# BBPS_SMD.net
KiCad netlist of a schematic drawn in EAGLE
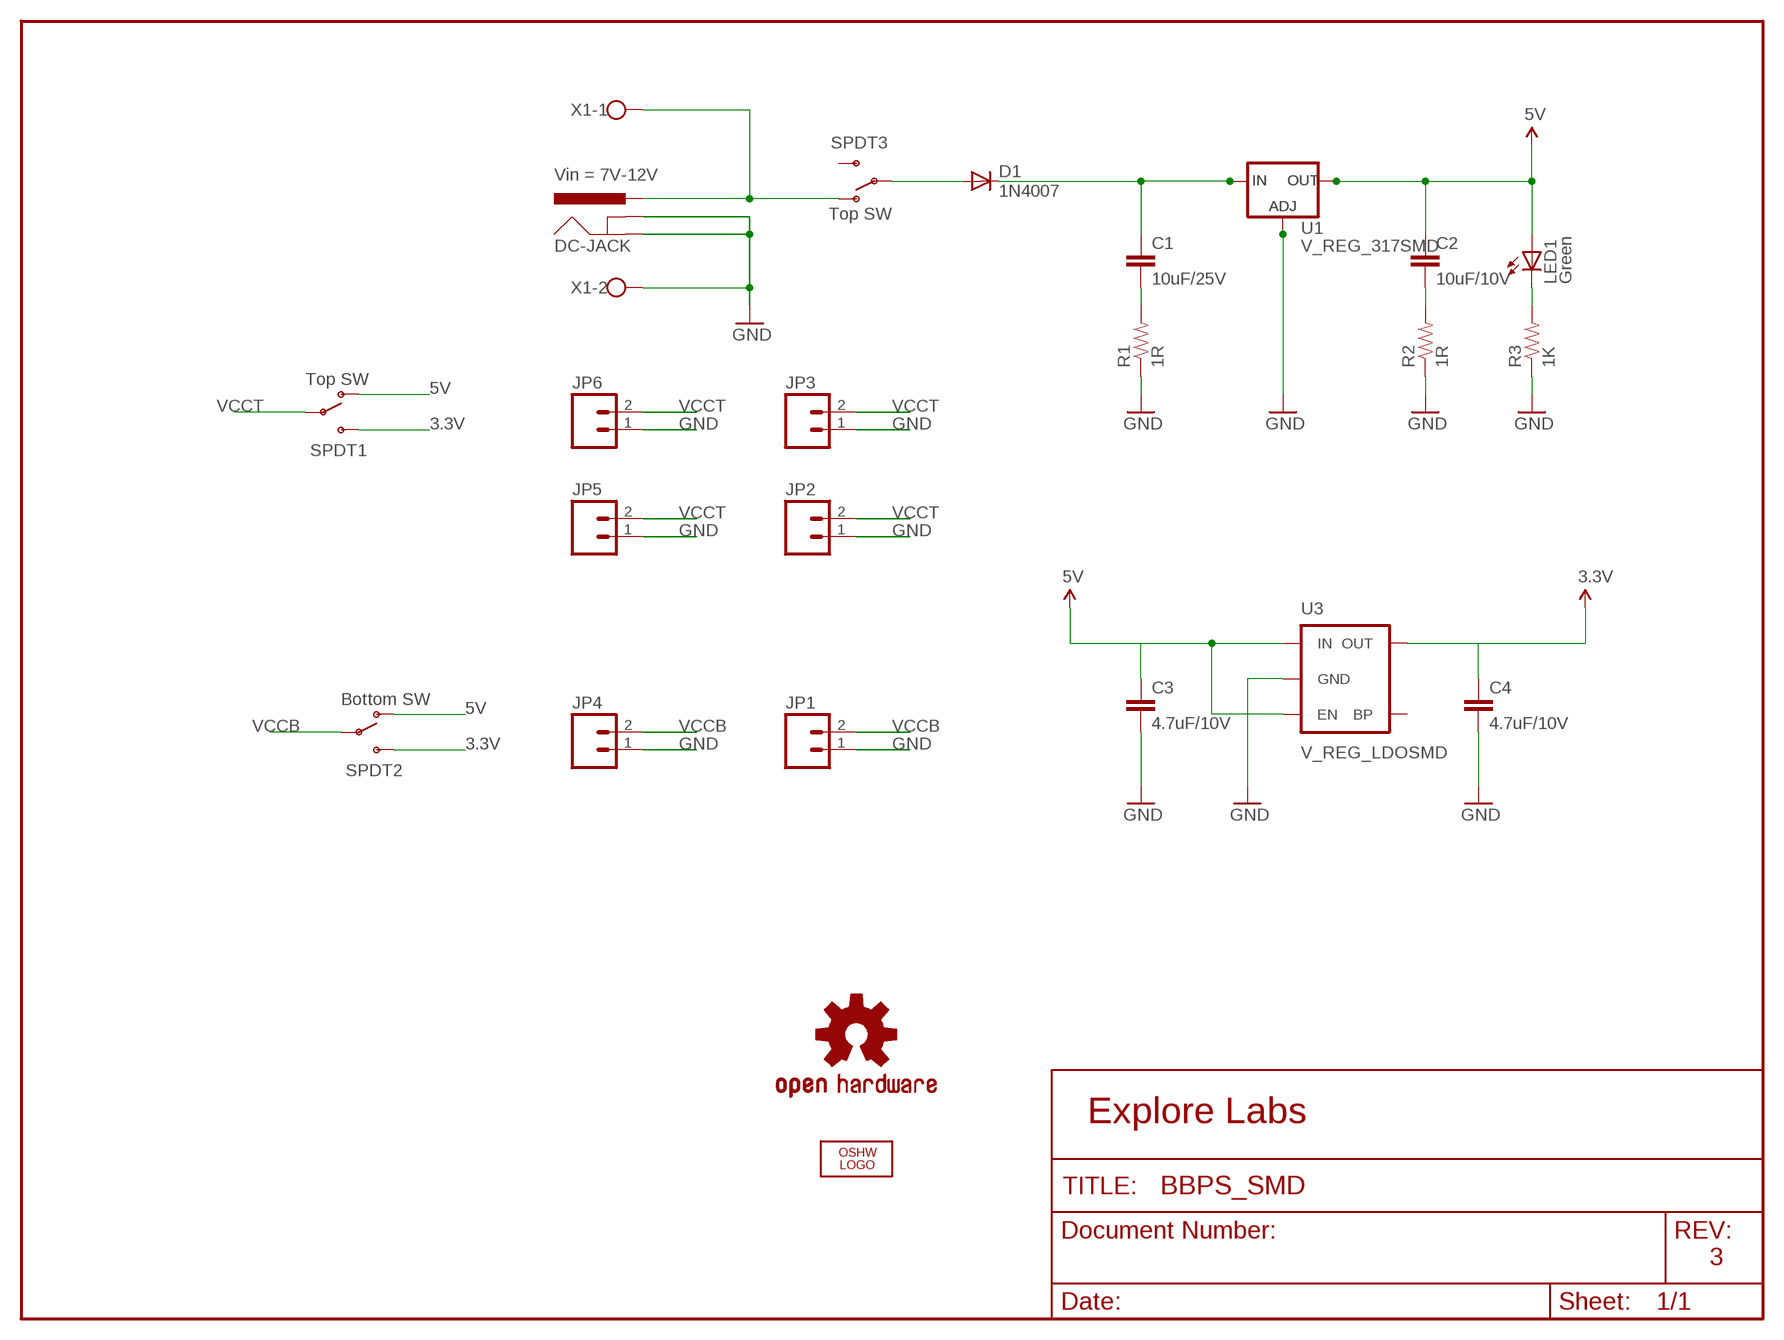
[diagram p0: schematic, sheet 1]

(export (version "E")
  (design (tool "Eeschema 10.0.6"))
  (components
    (comp (ref "C1")
      (value "10uF/25V")
      (footprint "eagle-import:0603-CAP")
      (libsource (lib "eagle-import") (part "CAP0603-CAP"))
    )
    (comp (ref "C2")
      (value "10uF/10V")
      (footprint "eagle-import:0603-CAP")
      (libsource (lib "eagle-import") (part "CAP0603-CAP"))
    )
    (comp (ref "C3")
      (value "4.7uF/10V")
      (footprint "eagle-import:0603-CAP")
      (libsource (lib "eagle-import") (part "CAP0603-CAP"))
    )
    (comp (ref "C4")
      (value "4.7uF/10V")
      (footprint "eagle-import:0603-CAP")
      (libsource (lib "eagle-import") (part "CAP0603-CAP"))
    )
    (comp (ref "D1")
      (value "1N4007")
      (footprint "eagle-import:SMA-DIODE-KIT")
      (libsource (lib "eagle-import") (part "DIODESMA-KIT"))
    )
    (comp (ref "DC-JACK")
      (value "Vin = 7V-12V")
      (footprint "eagle-import:POWER_JACK_PTH")
      (libsource (lib "eagle-import") (part "POWER_JACKPTH"))
    )
    (comp (ref "JP1")
      (value "M02PTH")
      (footprint "eagle-import:1X02")
      (libsource (lib "eagle-import") (part "M02PTH"))
    )
    (comp (ref "JP2")
      (value "M02PTH")
      (footprint "eagle-import:1X02")
      (libsource (lib "eagle-import") (part "M02PTH"))
    )
    (comp (ref "JP3")
      (value "M02PTH")
      (footprint "eagle-import:1X02")
      (libsource (lib "eagle-import") (part "M02PTH"))
    )
    (comp (ref "JP4")
      (value "M02PTH")
      (footprint "eagle-import:1X02")
      (libsource (lib "eagle-import") (part "M02PTH"))
    )
    (comp (ref "JP5")
      (value "M02PTH")
      (footprint "eagle-import:1X02")
      (libsource (lib "eagle-import") (part "M02PTH"))
    )
    (comp (ref "JP6")
      (value "M02PTH")
      (footprint "eagle-import:1X02")
      (libsource (lib "eagle-import") (part "M02PTH"))
    )
    (comp (ref "LED1")
      (value "Green")
      (footprint "eagle-import:CHIPLED_0805")
      (libsource (lib "eagle-import") (part "LEDCHIPLED_0805"))
    )
    (comp (ref "LOGO2")
      (value "OSHW_LOGO_FILLX0100-NT")
      (footprint "eagle-import:OSHW_FILLX100_NOTEXT")
      (libsource (lib "eagle-import") (part "OSHW_LOGO_FILLX0100-NT"))
    )
    (comp (ref "R1")
      (value "1R")
      (footprint "eagle-import:0603-RES")
      (libsource (lib "eagle-import") (part "RESISTOR0603-RES"))
    )
    (comp (ref "R2")
      (value "1R")
      (footprint "eagle-import:0603-RES")
      (libsource (lib "eagle-import") (part "RESISTOR0603-RES"))
    )
    (comp (ref "R3")
      (value "1K")
      (footprint "eagle-import:0603-RES")
      (libsource (lib "eagle-import") (part "RESISTOR0603-RES"))
    )
    (comp (ref "SPDT1")
      (value "Top SW")
      (footprint "eagle-import:SWITCH-SPDT")
      (libsource (lib "eagle-import") (part "SWITCH-SPSTPTH"))
    )
    (comp (ref "SPDT2")
      (value "Bottom SW")
      (footprint "eagle-import:SWITCH-SPDT")
      (libsource (lib "eagle-import") (part "SWITCH-SPSTPTH"))
    )
    (comp (ref "SPDT3")
      (value "Top SW")
      (footprint "eagle-import:SWITCH-SPDT")
      (libsource (lib "eagle-import") (part "SWITCH-SPSTPTH"))
    )
    (comp (ref "U$3")
      (value "OSHW-LOGOM")
      (footprint "eagle-import:OSHW-LOGO-M")
      (libsource (lib "eagle-import") (part "OSHW-LOGOM"))
    )
    (comp (ref "U1")
      (value "V_REG_317SMD")
      (footprint "eagle-import:SOT223")
      (libsource (lib "eagle-import") (part "V_REG_317SMD"))
    )
    (comp (ref "U2")
      (value "V_REG_317DPACK")
      (footprint "eagle-import:V-REG_DPACK")
      (libsource (lib "eagle-import") (part "V_REG_317DPACK"))
    )
    (comp (ref "U3")
      (value "V_REG_LDOSMD")
      (footprint "eagle-import:SOT23-5")
      (libsource (lib "eagle-import") (part "V_REG_LDOSMD"))
    )
    (comp (ref "X1")
      (value "W237-102")
      (footprint "eagle-import:W237-102")
      (fields (field (name "MPN") "237-102"))
      (libsource (lib "eagle-import") (part "W237-102"))
    )
  )
  (nets
    (net (code "1") (name "/VCCB") (class "Default")
      (node (ref "JP1") (pin "2") (pinfunction "2_2") (pintype "passive"))
      (node (ref "JP4") (pin "2") (pinfunction "2_2") (pintype "passive"))
      (node (ref "SPDT2") (pin "2") (pinfunction "P_2") (pintype "passive"))
    )
    (net (code "2") (name "/VCCT") (class "Default")
      (node (ref "JP2") (pin "2") (pinfunction "2_2") (pintype "passive"))
      (node (ref "JP3") (pin "2") (pinfunction "2_2") (pintype "passive"))
      (node (ref "JP5") (pin "2") (pinfunction "2_2") (pintype "passive"))
      (node (ref "JP6") (pin "2") (pinfunction "2_2") (pintype "passive"))
      (node (ref "SPDT1") (pin "2") (pinfunction "P_2") (pintype "passive"))
    )
    (net (code "3") (name "3.3V") (class "Default")
      (node (ref "C4") (pin "1") (pinfunction "1_1") (pintype "passive"))
      (node (ref "SPDT1") (pin "3") (pinfunction "S_3") (pintype "passive"))
      (node (ref "SPDT2") (pin "3") (pinfunction "S_3") (pintype "passive"))
      (node (ref "U3") (pin "5") (pinfunction "OUT_5") (pintype "passive"))
    )
    (net (code "4") (name "5V") (class "Default")
      (node (ref "C2") (pin "1") (pinfunction "1_1") (pintype "passive"))
      (node (ref "C3") (pin "1") (pinfunction "1_1") (pintype "passive"))
      (node (ref "LED1") (pin "A") (pinfunction "A_A") (pintype "passive"))
      (node (ref "SPDT1") (pin "1") (pinfunction "O_1") (pintype "passive"))
      (node (ref "SPDT2") (pin "1") (pinfunction "O_1") (pintype "passive"))
      (node (ref "U1") (pin "2") (pinfunction "OUT_2") (pintype "output"))
      (node (ref "U2") (pin "4") (pinfunction "OUT_4") (pintype "output"))
      (node (ref "U3") (pin "1") (pinfunction "IN_1") (pintype "input"))
      (node (ref "U3") (pin "3") (pinfunction "EN_3") (pintype "input"))
    )
    (net (code "5") (name "GND") (class "Default")
      (node (ref "C3") (pin "2") (pinfunction "2_2") (pintype "passive"))
      (node (ref "C4") (pin "2") (pinfunction "2_2") (pintype "passive"))
      (node (ref "DC-JACK") (pin "GND") (pinfunction "GND_GND") (pintype "bidirectional"))
      (node (ref "DC-JACK") (pin "GNDBREAK") (pinfunction "GNDBREAK_GNDBREAK") (pintype "bidirectional"))
      (node (ref "JP1") (pin "1") (pinfunction "1_1") (pintype "passive"))
      (node (ref "JP2") (pin "1") (pinfunction "1_1") (pintype "passive"))
      (node (ref "JP3") (pin "1") (pinfunction "1_1") (pintype "passive"))
      (node (ref "JP4") (pin "1") (pinfunction "1_1") (pintype "passive"))
      (node (ref "JP5") (pin "1") (pinfunction "1_1") (pintype "passive"))
      (node (ref "JP6") (pin "1") (pinfunction "1_1") (pintype "passive"))
      (node (ref "R1") (pin "1") (pinfunction "1_1") (pintype "passive"))
      (node (ref "R2") (pin "1") (pinfunction "1_1") (pintype "passive"))
      (node (ref "R3") (pin "1") (pinfunction "1_1") (pintype "passive"))
      (node (ref "U1") (pin "1") (pinfunction "ADJ_1") (pintype "input"))
      (node (ref "U2") (pin "1") (pinfunction "ADJ_1") (pintype "input"))
      (node (ref "U3") (pin "2") (pinfunction "GND_2") (pintype "input"))
      (node (ref "X1") (pin "2") (pinfunction "KL_2") (pintype "passive"))
    )
    (net (code "6") (name "Net-(C1-Pad2)") (class "Default")
      (node (ref "C1") (pin "2") (pinfunction "2_2") (pintype "passive"))
      (node (ref "R1") (pin "2") (pinfunction "2_2") (pintype "passive"))
    )
    (net (code "7") (name "Net-(C2-Pad2)") (class "Default")
      (node (ref "C2") (pin "2") (pinfunction "2_2") (pintype "passive"))
      (node (ref "R2") (pin "2") (pinfunction "2_2") (pintype "passive"))
    )
    (net (code "8") (name "Net-(LED1-PadC)") (class "Default")
      (node (ref "LED1") (pin "C") (pinfunction "C_C") (pintype "passive"))
      (node (ref "R3") (pin "2") (pinfunction "2_2") (pintype "passive"))
    )
    (net (code "9") (name "Net-(SPDT3-O)") (class "Default")
      (node (ref "DC-JACK") (pin "PWR") (pinfunction "PWR_PWR") (pintype "bidirectional"))
      (node (ref "SPDT3") (pin "1") (pinfunction "O_1") (pintype "passive"))
      (node (ref "X1") (pin "1") (pinfunction "KL_1") (pintype "passive"))
    )
    (net (code "10") (name "Net-(SPDT3-P)") (class "Default")
      (node (ref "D1") (pin "A") (pinfunction "A_A") (pintype "passive"))
      (node (ref "SPDT3") (pin "2") (pinfunction "P_2") (pintype "passive"))
    )
    (net (code "11") (name "Net-(U1-IN)") (class "Default")
      (node (ref "C1") (pin "1") (pinfunction "1_1") (pintype "passive"))
      (node (ref "D1") (pin "C") (pinfunction "C_C") (pintype "passive"))
      (node (ref "U1") (pin "3") (pinfunction "IN_3") (pintype "input"))
      (node (ref "U2") (pin "3") (pinfunction "IN_3") (pintype "input"))
    )
    (net (code "12") (name "unconnected-(SPDT3-S-Pad3)") (class "Default")
      (node (ref "SPDT3") (pin "3") (pinfunction "S_3") (pintype "passive"))
    )
    (net (code "13") (name "unconnected-(U3-BP-Pad4)") (class "Default")
      (node (ref "U3") (pin "4") (pinfunction "BP_4") (pintype "input"))
    )
  )
)
